# Power.net
KiCad netlist of a schematic drawn in Altium Designer
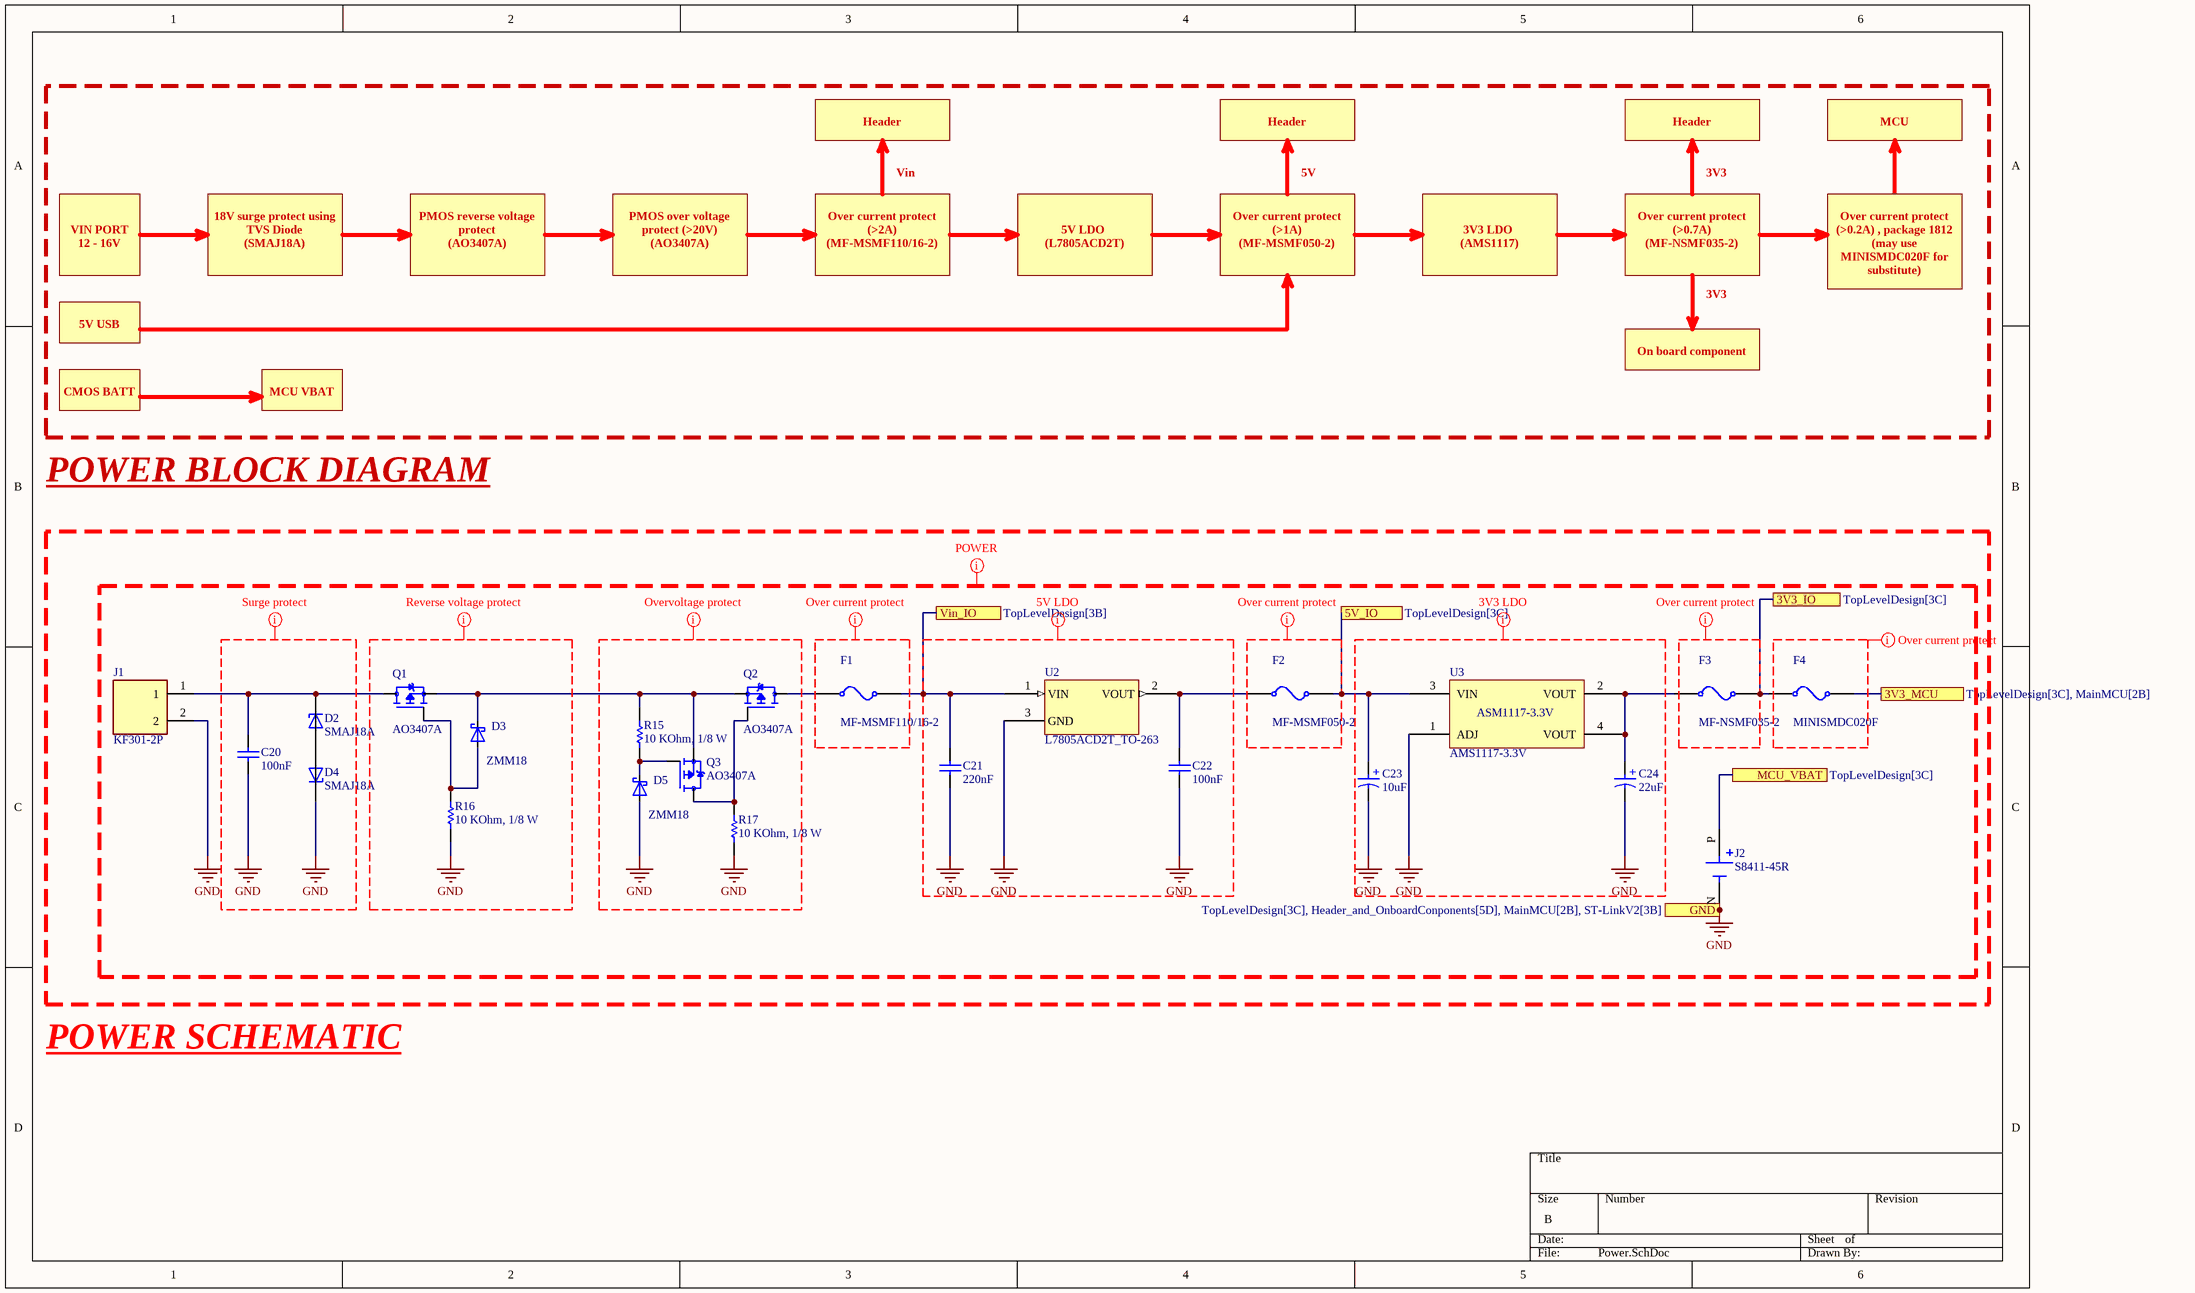
[diagram p0: Power.SchDoc]

(export (version "E")
  (design (tool "Eeschema 10.0.6"))
  (components
    (comp (ref "C20")
      (value "100nF")
      (footprint "CAP_0805")
      (description "CAP, size 0805, 0.1 nF, 50 VDC")
      (fields
        (field (name "TOLERANCE") "10%")
        (field (name "Comment") "0108051041050")
        (field (name "SOURCE") "Capacitor_0805_10_percent.SchLib")
      )
      (libsource (lib "Tin Tran") (part "0108056841050"))
    )
    (comp (ref "C21")
      (value "220nF")
      (footprint "CAP_0603")
      (description "CAP, size 0603, 220 nF, 50 VDC")
      (fields
        (field (name "TOLERANCE") "10%")
        (field (name "Comment") "0106032241050")
        (field (name "SOURCE") "Capacitor_0603_10_percent.SchLib")
      )
      (libsource (lib "Tin Tran") (part "010603475106.3"))
    )
    (comp (ref "C22")
      (value "100nF")
      (footprint "CAP_0603")
      (description "CAP, size 0603, 100 nF, 50 VDC")
      (fields
        (field (name "TOLERANCE") "10%")
        (field (name "Comment") "0106031041050")
        (field (name "SOURCE") "Capacitor_0603_10_percent.SchLib")
      )
      (libsource (lib "Tin Tran") (part "010603475106.3"))
    )
    (comp (ref "C23")
      (value "10uF")
      (footprint "WCAP-ASLI_D4H5.5")
      (description "V-Chip, D4 x H5.5mm, 10uF, 16V")
      (fields (field (name "MANUFACTURER") "Wurth Elektronik"))
      (libsource (lib "Tin Tran") (part "0710101508650801570160U20"))
    )
    (comp (ref "C24")
      (value "22uF")
      (footprint "WCAP-ASLI_D6.3H7.7")
      (description "V-Chip, D6.3 x H7.7mm, 22uF, 63V")
      (fields (field (name "MANUFACTURER") "Wurth Elektronik"))
      (libsource (lib "Tin Tran") (part "0710101508650801570160U20"))
    )
    (comp (ref "D2")
      (value "SMAJ18A")
      (footprint "DIOM4325X250N")
      (description "400W, 21.1V, 5%, Unidirectional, TVS")
      (fields (field (name "MF") "Taiwan Semiconductor"))
      (libsource (lib "Tin Tran") (part "SMAJ18A"))
    )
    (comp (ref "D3")
      (value "ZMM18")
      (footprint "SOD-80_MiniMELF_Glass")
      (libsource (lib "Tin Tran") (part "Schottky-Diode"))
    )
    (comp (ref "D4")
      (value "SMAJ18A")
      (footprint "DIOM4325X250N")
      (description "400W, 21.1V, 5%, Unidirectional, TVS")
      (fields (field (name "MF") "Taiwan Semiconductor"))
      (libsource (lib "Tin Tran") (part "SMAJ18A"))
    )
    (comp (ref "D5")
      (value "ZMM18")
      (footprint "SOD-80_MiniMELF_Glass")
      (libsource (lib "Tin Tran") (part "Schottky-Diode"))
    )
    (comp (ref "F1")
      (value "MF-MSMF110/16-2")
      (footprint "Fuse_SMD_1812")
      (description "Resettable Fuse, Size 1812, 16V, 1.1A")
      (fields (field (name "MANUFACTURER") "Bourns"))
      (libsource (lib "Tin Tran") (part "061812110016"))
    )
    (comp (ref "F2")
      (value "MF-MSMF050-2")
      (footprint "Fuse_SMD_1812")
      (description "Resettable Fuse, Size 1812, 15V, 0.5A")
      (fields (field (name "MANUFACTURER") "Bourns"))
      (libsource (lib "Tin Tran") (part "061812050015"))
    )
    (comp (ref "F3")
      (value "MF-NSMF035-2")
      (footprint "Fuse_SMD_1206")
      (description "Resettable Fuse, Size 1206, 6V, 0.35A")
      (fields (field (name "MANUFACTURER") "Bourns"))
      (libsource (lib "Tin Tran") (part "061812110016"))
    )
    (comp (ref "F4")
      (value "MINISMDC020F")
      (footprint "Fuse_SMD_1812")
      (description "Resettable Fuse, Size 1812, 30V, 0.2A")
      (fields (field (name "MANUFACTURER") "Bourns"))
      (libsource (lib "Tin Tran") (part "061812300006"))
    )
    (comp (ref "J1")
      (value "KF301-2P")
      (footprint "HANDSON_KF301-2P")
      (description "2 Pin Terminal Block 5mm Pitch")
      (libsource (lib "Tin Tran") (part "KF301-2P"))
    )
    (comp (ref "J2")
      (value "S8411-45R")
      (footprint "HARWIN_S8411-45R")
      (description "Coin Cell Battery Retainer, Horizontal SMT, for CR1220 Coin Cell Batteries, Tape & Reeled")
      (fields (field (name "MF") "Harwin"))
      (libsource (lib "Tin Tran") (part "S8411-45R"))
    )
    (comp (ref "Q1")
      (value "AO3407A")
      (footprint "SOT95P280X125-3N")
      (description "P-Channel 30 V 4.3A (Ta) 1.4W (Ta) Surface Mount SOT-23-3")
      (fields (field (name "MF") "Alpha &"))
      (libsource (lib "Tin Tran") (part "AO3407A"))
    )
    (comp (ref "Q2")
      (value "AO3407A")
      (footprint "SOT95P280X125-3N")
      (description "P-Channel 30 V 4.3A (Ta) 1.4W (Ta) Surface Mount SOT-23-3")
      (fields (field (name "MF") "Alpha &"))
      (libsource (lib "Tin Tran") (part "AO3407A"))
    )
    (comp (ref "Q3")
      (value "AO3407A")
      (footprint "SOT95P280X125-3N")
      (description "P-Channel 30 V 4.3A (Ta) 1.4W (Ta) Surface Mount SOT-23-3")
      (fields (field (name "MF") "Alpha &"))
      (libsource (lib "Tin Tran") (part "AO3407A"))
    )
    (comp (ref "R15")
      (value "10 KOhm, 1/8 W")
      (footprint "RESISTOR_0805")
      (description "RES, size 0805, 10 KOhm, 1/8 W")
      (fields (field (name "Comment") "0008051031"))
      (libsource (lib "Tin Tran") (part "0008052035_1"))
    )
    (comp (ref "R16")
      (value "10 KOhm, 1/8 W")
      (footprint "RESISTOR_0805")
      (description "RES, size 0805, 10 KOhm, 1/8 W")
      (fields (field (name "Comment") "0008051031"))
      (libsource (lib "Tin Tran") (part "0008052035_1"))
    )
    (comp (ref "R17")
      (value "10 KOhm, 1/8 W")
      (footprint "RESISTOR_0805")
      (description "RES, size 0805, 10 KOhm, 1/8 W")
      (fields (field (name "Comment") "0008051031"))
      (libsource (lib "Tin Tran") (part "0008052035_1"))
    )
    (comp (ref "U2")
      (value "L7805ACD2T_TO-263")
      (footprint "TO-263")
      (description "Out: 5V, 1.5A; In: 7V to 35V; Pacakge: TO-263")
      (libsource (lib "Tin Tran") (part "L78M09ABDT-TR_TO-252"))
    )
    (comp (ref "U3")
      (value "AMS1117-3.3V")
      (footprint "AMS1117-3.3V SOT223")
      (description "AMS1117-3.3V, OUT 3.3V 1A.")
      (fields (field (name "MANUFACTURER") "AMS") (field (name "SOURCE") "AMS_family.SchLib"))
      (libsource (lib "Tin Tran") (part "AMS1117-3.3V"))
    )
  )
  (nets
    (net (code "1") (name "/3V3_IO") (class "Default")
      (node (ref "F3") (pin "1") (pinfunction "1_1") (pintype "passive"))
      (node (ref "F4") (pin "0") (pinfunction "0_0") (pintype "passive"))
    )
    (net (code "2") (name "/3V3_MCU") (class "Default")
      (node (ref "F4") (pin "1") (pinfunction "1_1") (pintype "passive"))
    )
    (net (code "3") (name "/5V_IO") (class "Default")
      (node (ref "C23") (pin "1") (pinfunction "P_1") (pintype "passive"))
      (node (ref "F2") (pin "1") (pinfunction "1_1") (pintype "passive"))
      (node (ref "U3") (pin "3") (pinfunction "VIN_3") (pintype "passive"))
    )
    (net (code "4") (name "/MCU_VBAT") (class "Default")
      (node (ref "J2") (pin "P") (pinfunction "POS_P") (pintype "passive"))
    )
    (net (code "5") (name "/Vin_IO") (class "Default")
      (node (ref "C21") (pin "2") (pinfunction "2_2") (pintype "passive"))
      (node (ref "F1") (pin "1") (pinfunction "1_1") (pintype "passive"))
      (node (ref "U2") (pin "1") (pinfunction "VIN_1") (pintype "input"))
    )
    (net (code "6") (name "GND") (class "Default")
      (node (ref "C20") (pin "1") (pinfunction "1_1") (pintype "passive"))
      (node (ref "C21") (pin "1") (pinfunction "1_1") (pintype "passive"))
      (node (ref "C22") (pin "1") (pinfunction "1_1") (pintype "passive"))
      (node (ref "C23") (pin "2") (pinfunction "N_2") (pintype "passive"))
      (node (ref "C24") (pin "2") (pinfunction "N_2") (pintype "passive"))
      (node (ref "D4") (pin "C") (pinfunction "C_C") (pintype "passive"))
      (node (ref "D5") (pin "A") (pinfunction "A_A") (pintype "passive"))
      (node (ref "J1") (pin "2") (pinfunction "2_2") (pintype "passive"))
      (node (ref "J2") (pin "N") (pinfunction "NEG_N") (pintype "passive"))
      (node (ref "R16") (pin "1") (pinfunction "1_1") (pintype "passive"))
      (node (ref "R17") (pin "1") (pinfunction "1_1") (pintype "passive"))
      (node (ref "U2") (pin "3") (pinfunction "GND_3") (pintype "passive"))
      (node (ref "U3") (pin "1") (pinfunction "ADJ_1") (pintype "power_in"))
    )
    (net (code "7") (name "Net-(C24-P)") (class "Default")
      (node (ref "C24") (pin "1") (pinfunction "P_1") (pintype "passive"))
      (node (ref "F3") (pin "0") (pinfunction "0_0") (pintype "passive"))
      (node (ref "U3") (pin "2") (pinfunction "VOUT_2") (pintype "passive"))
      (node (ref "U3") (pin "4") (pinfunction "VOUT_4") (pintype "power_in"))
    )
    (net (code "8") (name "Net-(D2-PadA)") (class "Default")
      (node (ref "D2") (pin "A") (pinfunction "A_A") (pintype "passive"))
      (node (ref "D4") (pin "A") (pinfunction "A_A") (pintype "passive"))
    )
    (net (code "9") (name "Net-(Q1-D)") (class "Default")
      (node (ref "C20") (pin "2") (pinfunction "2_2") (pintype "passive"))
      (node (ref "D2") (pin "C") (pinfunction "C_C") (pintype "passive"))
      (node (ref "J1") (pin "1") (pinfunction "1_1") (pintype "passive"))
      (node (ref "Q1") (pin "3") (pinfunction "D_3") (pintype "passive"))
    )
    (net (code "10") (name "Net-(Q1-G)") (class "Default")
      (node (ref "D3") (pin "A") (pinfunction "A_A") (pintype "passive"))
      (node (ref "Q1") (pin "1") (pinfunction "G_1") (pintype "passive"))
      (node (ref "R16") (pin "2") (pinfunction "2_2") (pintype "passive"))
    )
    (net (code "11") (name "Net-(Q1-S)") (class "Default")
      (node (ref "D3") (pin "K") (pinfunction "K_K") (pintype "passive"))
      (node (ref "Q1") (pin "2") (pinfunction "S_2") (pintype "passive"))
      (node (ref "Q2") (pin "2") (pinfunction "S_2") (pintype "passive"))
      (node (ref "Q3") (pin "2") (pinfunction "S_2") (pintype "passive"))
      (node (ref "R15") (pin "2") (pinfunction "2_2") (pintype "passive"))
    )
    (net (code "12") (name "Net-(Q2-D)") (class "Default")
      (node (ref "F1") (pin "0") (pinfunction "0_0") (pintype "passive"))
      (node (ref "Q2") (pin "3") (pinfunction "D_3") (pintype "passive"))
    )
    (net (code "13") (name "Net-(Q2-G)") (class "Default")
      (node (ref "Q2") (pin "1") (pinfunction "G_1") (pintype "passive"))
      (node (ref "Q3") (pin "3") (pinfunction "D_3") (pintype "passive"))
      (node (ref "R17") (pin "2") (pinfunction "2_2") (pintype "passive"))
    )
    (net (code "14") (name "Net-(Q3-G)") (class "Default")
      (node (ref "D5") (pin "K") (pinfunction "K_K") (pintype "passive"))
      (node (ref "Q3") (pin "1") (pinfunction "G_1") (pintype "passive"))
      (node (ref "R15") (pin "1") (pinfunction "1_1") (pintype "passive"))
    )
    (net (code "15") (name "Net-(U2-VOUT)") (class "Default")
      (node (ref "C22") (pin "2") (pinfunction "2_2") (pintype "passive"))
      (node (ref "F2") (pin "0") (pinfunction "0_0") (pintype "passive"))
      (node (ref "U2") (pin "2") (pinfunction "VOUT_2") (pintype "output"))
    )
  )
)
